# MPPT-v2.net
KiCad netlist of a schematic drawn in Altium Designer
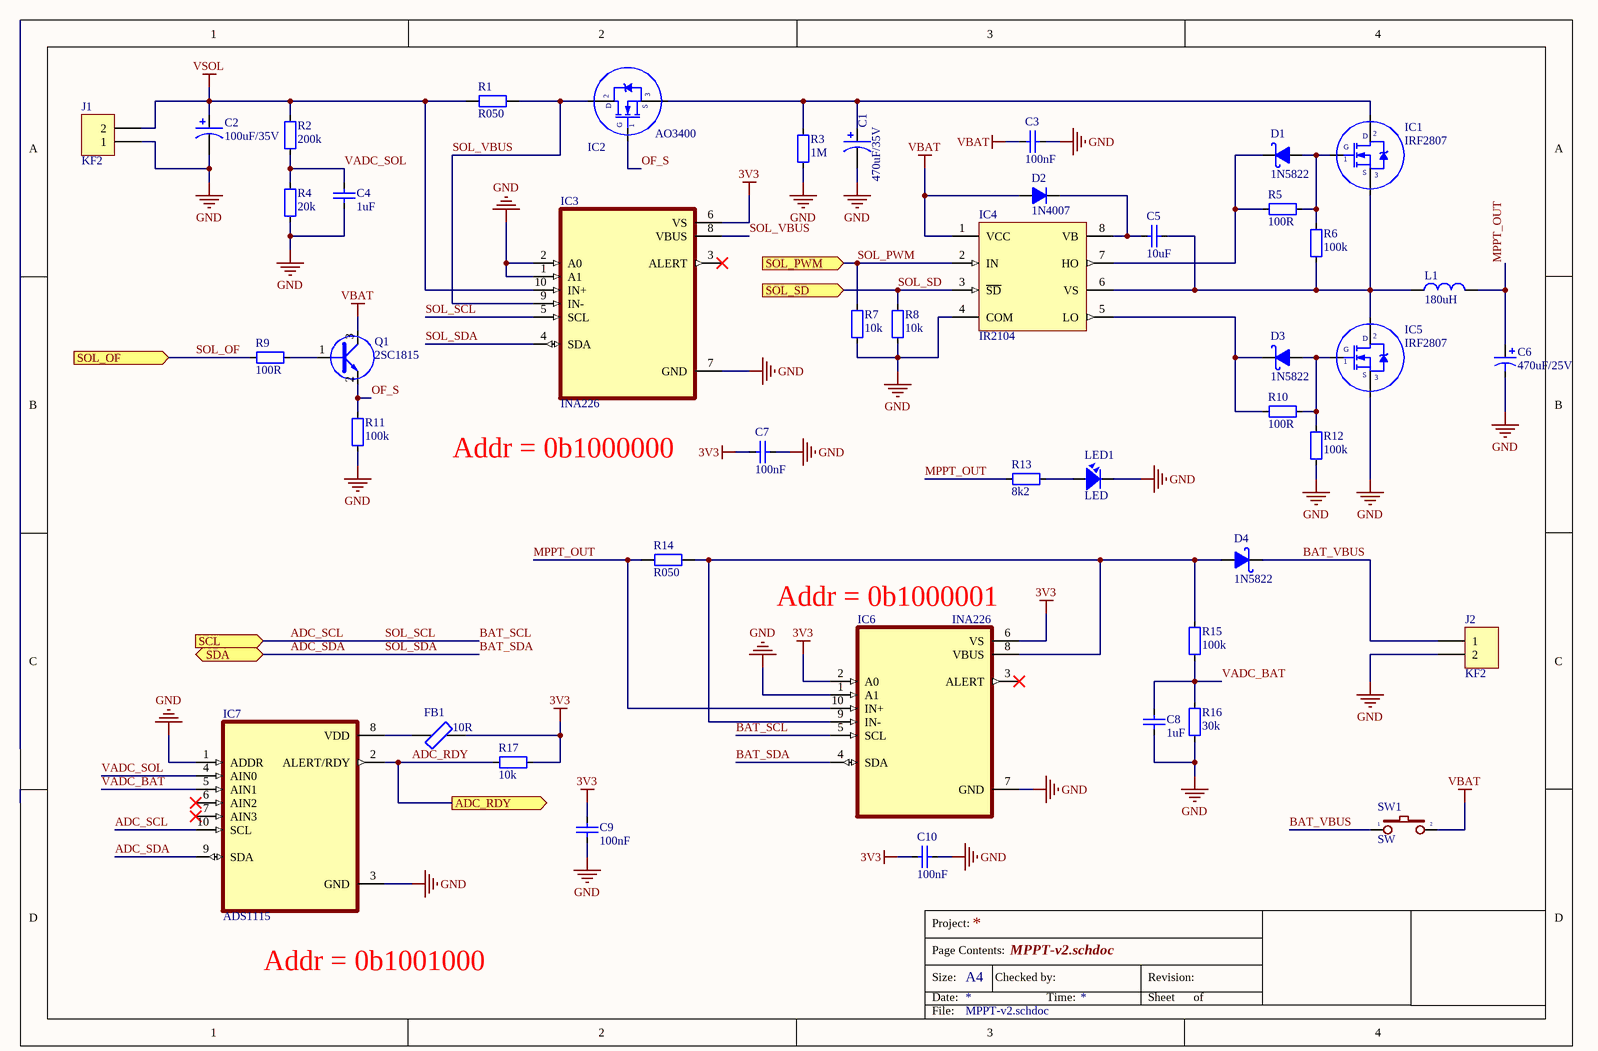
[diagram p0: MPPT-v2.schdoc]

(export (version "E")
  (design (tool "Eeschema 10.0.6"))
  (components
    (comp (ref "C1")
      (value "470uF/35V")
      (footprint "CAP_H17_D10")
      (description "Polarized Capacitor (Axial)")
      (fields (field (name "PUBLISHER") "Altium Limited"))
      (libsource (lib "My Library") (part "Cap Pol"))
    )
    (comp (ref "C2")
      (value "100uF/35V")
      (footprint "CAP_H12_D06")
      (description "Polarized Capacitor (Axial)")
      (fields (field (name "PUBLISHER") "Altium Limited"))
      (libsource (lib "My Library") (part "Cap Pol"))
    )
    (comp (ref "C3")
      (value "100nF")
      (footprint "CAP_0805")
      (description "Capacitor")
      (fields (field (name "PUBLISHER") "Altium Limited"))
      (libsource (lib "My Library") (part "CapSMD"))
    )
    (comp (ref "C4")
      (value "1uF")
      (footprint "CAP_0805")
      (description "Capacitor")
      (fields (field (name "PUBLISHER") "Altium Limited"))
      (libsource (lib "My Library") (part "CapSMD"))
    )
    (comp (ref "C5")
      (value "10uF")
      (footprint "CAP_0805")
      (description "Capacitor")
      (fields (field (name "PUBLISHER") "Altium Limited"))
      (libsource (lib "My Library") (part "CapSMD"))
    )
    (comp (ref "C6")
      (value "470uF/25V")
      (footprint "C8mm")
      (description "Polarized Capacitor (Axial)")
      (fields (field (name "PUBLISHER") "Altium Limited"))
      (libsource (lib "") (part "Cap Pol_1"))
    )
    (comp (ref "C7")
      (value "100nF")
      (footprint "CAP_0805")
      (description "Capacitor")
      (fields (field (name "PUBLISHER") "Altium Limited"))
      (libsource (lib "My Library") (part "CapSMD"))
    )
    (comp (ref "C8")
      (value "1uF")
      (footprint "CAP_0805")
      (description "Capacitor")
      (fields (field (name "PUBLISHER") "Altium Limited"))
      (libsource (lib "My Library") (part "CapSMD"))
    )
    (comp (ref "C9")
      (value "100nF")
      (footprint "CAP_0805")
      (description "Capacitor")
      (fields (field (name "PUBLISHER") "Altium Limited"))
      (libsource (lib "My Library") (part "CapSMD"))
    )
    (comp (ref "C10")
      (value "100nF")
      (footprint "CAP_0805")
      (description "Capacitor")
      (fields (field (name "PUBLISHER") "Altium Limited"))
      (libsource (lib "My Library") (part "CapSMD"))
    )
    (comp (ref "D1")
      (value "1N5822")
      (footprint "DIO-214AC(SMA)")
      (description "Schottky Rectifiers")
      (libsource (lib "My Library") (part "1N5822"))
    )
    (comp (ref "D2")
      (value "1N4007")
      (footprint "DIO-214AC(SMA)")
      (description "Diode 1A")
      (libsource (lib "My Library") (part "D1A"))
    )
    (comp (ref "D3")
      (value "1N5822")
      (footprint "DIO-214AC(SMA)")
      (description "Schottky Rectifiers")
      (libsource (lib "My Library") (part "1N5822"))
    )
    (comp (ref "D4")
      (value "1N5822")
      (footprint "DIO-214AC(SMA)")
      (description "Schottky Rectifiers")
      (libsource (lib "My Library") (part "1N5822"))
    )
    (comp (ref "FB1")
      (value "10R")
      (footprint "RES-SMD-0805")
      (description "Generic Ferrit Bead")
      (libsource (lib "My Library") (part "Ferrit Bead"))
    )
    (comp (ref "IC1")
      (value "IRF2807")
      (footprint "TO-220")
      (description "Generic N Channel MOSFET")
      (libsource (lib "My Library") (part "MOSFET_N"))
    )
    (comp (ref "IC2")
      (value "AO3400")
      (footprint "SOT23A")
      (description "Generic N Channel MOSFET")
      (libsource (lib "My Library") (part "MOSFET_N"))
    )
    (comp (ref "IC3")
      (value "INA226")
      (footprint "VSSOP-10")
      (description "Current Sensing IC")
      (libsource (lib "My Library") (part "INA226"))
    )
    (comp (ref "IC4")
      (value "IR2104")
      (footprint "SOP-8")
      (description "PWM Driver")
      (libsource (lib "My Library") (part "IR2104"))
    )
    (comp (ref "IC5")
      (value "IRF2807")
      (footprint "TO-220")
      (description "Generic N Channel MOSFET")
      (libsource (lib "My Library") (part "MOSFET_N"))
    )
    (comp (ref "IC6")
      (value "INA226")
      (footprint "VSSOP-10")
      (description "Current Sensing IC")
      (libsource (lib "My Library") (part "INA226"))
    )
    (comp (ref "IC7")
      (value "ADS1115")
      (footprint "VSSOP-10")
      (description "16 bits 4 channals ADC IC")
      (libsource (lib "My Library") (part "ADS1115"))
    )
    (comp (ref "J1")
      (value "KF2")
      (footprint "KF2-5.08")
      (fields
        (field (name "MANUFACTURER") "Würth Elektronik eiSos GmbH")
        (field (name "PARTNO") "691103110002")
        (field (name "CREATED BY") "Karrer Zheng")
      )
      (libsource (lib "My Library") (part "KF2"))
    )
    (comp (ref "J2")
      (value "KF2")
      (footprint "KF2-5.08")
      (fields
        (field (name "MANUFACTURER") "Würth Elektronik eiSos GmbH")
        (field (name "PARTNO") "691103110002")
        (field (name "CREATED BY") "Karrer Zheng")
      )
      (libsource (lib "") (part "KF2_1"))
    )
    (comp (ref "L1")
      (value "180uH")
      (footprint "L-DIP-M-13.5x6")
      (description "180uH 4A 13mm")
      (libsource (lib "My Library") (part "Inductor"))
    )
    (comp (ref "LED1")
      (value "LED")
      (footprint "LED-0805-Red")
      (description "LED Single colour Green and Red")
      (libsource (lib "My Library") (part "LED"))
    )
    (comp (ref "Q1")
      (value "2SC1815")
      (footprint "SOT23D")
      (description "NPN 600mW, ECB")
      (libsource (lib "My Library") (part "C1815"))
    )
    (comp (ref "R1")
      (value "R050")
      (footprint "RES-SMD-2512")
      (description "Resistor SMD")
      (fields
        (field (name "MANUFACTURER") "Generic Components")
        (field (name "PUBLISHER") "Altium Hobart Technology Centre")
      )
      (libsource (lib "") (part "Resistor - SMD_1"))
    )
    (comp (ref "R2")
      (value "200k")
      (footprint "RES-SMD-0805")
      (description "Resistor")
      (fields
        (field (name "MANUFACTURER") "Generic Components")
        (field (name "PUBLISHER") "Altium Hobart Technology Centre")
      )
      (libsource (lib "My Library") (part "Resistor - SMD"))
    )
    (comp (ref "R3")
      (value "1M")
      (footprint "RES-SMD-0805")
      (description "Resistor")
      (fields
        (field (name "MANUFACTURER") "Generic Components")
        (field (name "PUBLISHER") "Altium Hobart Technology Centre")
      )
      (libsource (lib "My Library") (part "Resistor - SMD"))
    )
    (comp (ref "R4")
      (value "20k")
      (footprint "RES-SMD-0805")
      (description "Resistor")
      (fields
        (field (name "MANUFACTURER") "Generic Components")
        (field (name "PUBLISHER") "Altium Hobart Technology Centre")
      )
      (libsource (lib "My Library") (part "Resistor - SMD"))
    )
    (comp (ref "R5")
      (value "100R")
      (footprint "RES-SMD-0805")
      (description "Resistor")
      (fields
        (field (name "MANUFACTURER") "Generic Components")
        (field (name "PUBLISHER") "Altium Hobart Technology Centre")
      )
      (libsource (lib "My Library") (part "Resistor - SMD"))
    )
    (comp (ref "R6")
      (value "100k")
      (footprint "RES-SMD-0805")
      (description "Resistor")
      (fields
        (field (name "MANUFACTURER") "Generic Components")
        (field (name "PUBLISHER") "Altium Hobart Technology Centre")
      )
      (libsource (lib "My Library") (part "Resistor - SMD"))
    )
    (comp (ref "R7")
      (value "10k")
      (footprint "RES-SMD-0805")
      (description "Resistor")
      (fields
        (field (name "MANUFACTURER") "Generic Components")
        (field (name "PUBLISHER") "Altium Hobart Technology Centre")
      )
      (libsource (lib "My Library") (part "Resistor - SMD"))
    )
    (comp (ref "R8")
      (value "10k")
      (footprint "RES-SMD-0805")
      (description "Resistor")
      (fields
        (field (name "MANUFACTURER") "Generic Components")
        (field (name "PUBLISHER") "Altium Hobart Technology Centre")
      )
      (libsource (lib "My Library") (part "Resistor - SMD"))
    )
    (comp (ref "R9")
      (value "100R")
      (footprint "RES-SMD-0805")
      (description "Resistor")
      (fields
        (field (name "MANUFACTURER") "Generic Components")
        (field (name "PUBLISHER") "Altium Hobart Technology Centre")
      )
      (libsource (lib "My Library") (part "Resistor - SMD"))
    )
    (comp (ref "R10")
      (value "100R")
      (footprint "RES-SMD-0805")
      (description "Resistor")
      (fields
        (field (name "MANUFACTURER") "Generic Components")
        (field (name "PUBLISHER") "Altium Hobart Technology Centre")
      )
      (libsource (lib "My Library") (part "Resistor - SMD"))
    )
    (comp (ref "R11")
      (value "100k")
      (footprint "RES-SMD-0805")
      (description "Resistor")
      (fields
        (field (name "MANUFACTURER") "Generic Components")
        (field (name "PUBLISHER") "Altium Hobart Technology Centre")
      )
      (libsource (lib "My Library") (part "Resistor - SMD"))
    )
    (comp (ref "R12")
      (value "100k")
      (footprint "RES-SMD-0805")
      (description "Resistor")
      (fields
        (field (name "MANUFACTURER") "Generic Components")
        (field (name "PUBLISHER") "Altium Hobart Technology Centre")
      )
      (libsource (lib "My Library") (part "Resistor - SMD"))
    )
    (comp (ref "R13")
      (value "8k2")
      (footprint "RES-SMD-0805")
      (description "Resistor")
      (fields
        (field (name "MANUFACTURER") "Generic Components")
        (field (name "PUBLISHER") "Altium Hobart Technology Centre")
      )
      (libsource (lib "My Library") (part "Resistor - SMD"))
    )
    (comp (ref "R14")
      (value "R050")
      (footprint "RES-SMD-2512")
      (description "Resistor SMD")
      (fields
        (field (name "MANUFACTURER") "Generic Components")
        (field (name "PUBLISHER") "Altium Hobart Technology Centre")
      )
      (libsource (lib "") (part "Resistor - SMD_1"))
    )
    (comp (ref "R15")
      (value "100k")
      (footprint "RES-SMD-0805")
      (description "Resistor")
      (fields
        (field (name "MANUFACTURER") "Generic Components")
        (field (name "PUBLISHER") "Altium Hobart Technology Centre")
      )
      (libsource (lib "My Library") (part "Resistor - SMD"))
    )
    (comp (ref "R16")
      (value "30k")
      (footprint "RES-SMD-0805")
      (description "Resistor")
      (fields
        (field (name "MANUFACTURER") "Generic Components")
        (field (name "PUBLISHER") "Altium Hobart Technology Centre")
      )
      (libsource (lib "My Library") (part "Resistor - SMD"))
    )
    (comp (ref "R17")
      (value "10k")
      (footprint "RES-SMD-0805")
      (description "Resistor")
      (fields
        (field (name "MANUFACTURER") "Generic Components")
        (field (name "PUBLISHER") "Altium Hobart Technology Centre")
      )
      (libsource (lib "My Library") (part "Resistor - SMD"))
    )
    (comp (ref "SW1")
      (value "SW")
      (footprint "SW2")
      (description "Switch button 2 pin")
      (libsource (lib "My Library") (part "SW2"))
    )
  )
  (nets
    (net (code "1") (name "/ADC_RDY") (class "Default")
      (node (ref "IC7") (pin "2") (pinfunction "ALERT/RDY_2") (pintype "output"))
      (node (ref "R17") (pin "2") (pinfunction "2_2") (pintype "passive"))
    )
    (net (code "2") (name "/ADC_SCL") (class "Default")
      (node (ref "IC3") (pin "5") (pinfunction "SCL_5") (pintype "input"))
      (node (ref "IC6") (pin "5") (pinfunction "SCL_5") (pintype "input"))
      (node (ref "IC7") (pin "10") (pinfunction "SCL_10") (pintype "input"))
    )
    (net (code "3") (name "/ADC_SDA") (class "Default")
      (node (ref "IC3") (pin "4") (pinfunction "SDA_4") (pintype "bidirectional"))
      (node (ref "IC6") (pin "4") (pinfunction "SDA_4") (pintype "bidirectional"))
      (node (ref "IC7") (pin "9") (pinfunction "SDA_9") (pintype "bidirectional"))
    )
    (net (code "4") (name "/BAT_VBUS") (class "Default")
      (node (ref "D4") (pin "2") (pinfunction "K_2") (pintype "passive"))
      (node (ref "J2") (pin "1") (pinfunction "1_1") (pintype "passive"))
      (node (ref "SW1") (pin "1") (pinfunction "1_1") (pintype "passive"))
    )
    (net (code "5") (name "/MPPT_OUT") (class "Default")
      (node (ref "C6") (pin "1") (pinfunction "1_1") (pintype "passive"))
      (node (ref "IC6") (pin "10") (pinfunction "IN+_10") (pintype "input"))
      (node (ref "L1") (pin "2") (pinfunction "2_2") (pintype "passive"))
      (node (ref "R13") (pin "1") (pinfunction "1_1") (pintype "passive"))
      (node (ref "R14") (pin "2") (pinfunction "2_2") (pintype "passive"))
    )
    (net (code "6") (name "/OF_S") (class "Default")
      (node (ref "IC2") (pin "1") (pinfunction "G_1") (pintype "passive"))
      (node (ref "Q1") (pin "2") (pinfunction "E_2") (pintype "passive"))
      (node (ref "R11") (pin "1") (pinfunction "1_1") (pintype "passive"))
    )
    (net (code "7") (name "/SOL_OF") (class "Default")
      (node (ref "R9") (pin "2") (pinfunction "2_2") (pintype "passive"))
    )
    (net (code "8") (name "/SOL_PWM") (class "Default")
      (node (ref "IC4") (pin "2") (pinfunction "IN_2") (pintype "input"))
      (node (ref "R7") (pin "2") (pinfunction "2_2") (pintype "passive"))
    )
    (net (code "9") (name "/SOL_SD") (class "Default")
      (node (ref "IC4") (pin "3") (pinfunction "~{SD}_3") (pintype "input"))
      (node (ref "R8") (pin "2") (pinfunction "2_2") (pintype "passive"))
    )
    (net (code "10") (name "/SOL_VBUS") (class "Default")
      (node (ref "IC2") (pin "2") (pinfunction "D_2") (pintype "passive"))
      (node (ref "IC3") (pin "8") (pinfunction "VBUS_8") (pintype "power_in"))
      (node (ref "IC3") (pin "9") (pinfunction "IN-_9") (pintype "input"))
      (node (ref "R1") (pin "1") (pinfunction "1_1") (pintype "passive"))
    )
    (net (code "11") (name "/VADC_BAT") (class "Default")
      (node (ref "C8") (pin "1") (pinfunction "1_1") (pintype "passive"))
      (node (ref "IC7") (pin "5") (pinfunction "AIN1_5") (pintype "input"))
      (node (ref "R15") (pin "2") (pinfunction "2_2") (pintype "passive"))
      (node (ref "R16") (pin "1") (pinfunction "1_1") (pintype "passive"))
    )
    (net (code "12") (name "/VADC_SOL") (class "Default")
      (node (ref "C4") (pin "1") (pinfunction "1_1") (pintype "passive"))
      (node (ref "IC7") (pin "4") (pinfunction "AIN0_4") (pintype "input"))
      (node (ref "R2") (pin "1") (pinfunction "1_1") (pintype "passive"))
      (node (ref "R4") (pin "1") (pinfunction "1_1") (pintype "passive"))
    )
    (net (code "13") (name "3V3") (class "Default")
      (node (ref "C10") (pin "1") (pinfunction "1_1") (pintype "passive"))
      (node (ref "C7") (pin "1") (pinfunction "1_1") (pintype "passive"))
      (node (ref "C9") (pin "1") (pinfunction "1_1") (pintype "passive"))
      (node (ref "FB1") (pin "2") (pintype "passive"))
      (node (ref "IC3") (pin "6") (pinfunction "VS_6") (pintype "power_in"))
      (node (ref "IC6") (pin "2") (pinfunction "A0_2") (pintype "input"))
      (node (ref "IC6") (pin "6") (pinfunction "VS_6") (pintype "power_in"))
      (node (ref "R17") (pin "1") (pinfunction "1_1") (pintype "passive"))
    )
    (net (code "14") (name "GND") (class "Default")
      (node (ref "C1") (pin "2") (pinfunction "2_2") (pintype "passive"))
      (node (ref "C10") (pin "2") (pinfunction "2_2") (pintype "passive"))
      (node (ref "C2") (pin "2") (pinfunction "2_2") (pintype "passive"))
      (node (ref "C3") (pin "2") (pinfunction "2_2") (pintype "passive"))
      (node (ref "C4") (pin "2") (pinfunction "2_2") (pintype "passive"))
      (node (ref "C6") (pin "2") (pinfunction "2_2") (pintype "passive"))
      (node (ref "C7") (pin "2") (pinfunction "2_2") (pintype "passive"))
      (node (ref "C8") (pin "2") (pinfunction "2_2") (pintype "passive"))
      (node (ref "C9") (pin "2") (pinfunction "2_2") (pintype "passive"))
      (node (ref "IC3") (pin "1") (pinfunction "A1_1") (pintype "input"))
      (node (ref "IC3") (pin "2") (pinfunction "A0_2") (pintype "input"))
      (node (ref "IC3") (pin "7") (pinfunction "GND_7") (pintype "power_in"))
      (node (ref "IC4") (pin "4") (pinfunction "COM_4") (pintype "power_in"))
      (node (ref "IC5") (pin "3") (pinfunction "S_3") (pintype "passive"))
      (node (ref "IC6") (pin "1") (pinfunction "A1_1") (pintype "input"))
      (node (ref "IC6") (pin "7") (pinfunction "GND_7") (pintype "power_in"))
      (node (ref "IC7") (pin "1") (pinfunction "ADDR_1") (pintype "input"))
      (node (ref "IC7") (pin "3") (pinfunction "GND_3") (pintype "power_in"))
      (node (ref "J1") (pin "1") (pinfunction "1_1") (pintype "passive"))
      (node (ref "J2") (pin "2") (pinfunction "2_2") (pintype "passive"))
      (node (ref "LED1") (pin "2") (pinfunction "2_2") (pintype "passive"))
      (node (ref "R11") (pin "2") (pinfunction "2_2") (pintype "passive"))
      (node (ref "R12") (pin "2") (pinfunction "2_2") (pintype "passive"))
      (node (ref "R16") (pin "2") (pinfunction "2_2") (pintype "passive"))
      (node (ref "R3") (pin "1") (pinfunction "1_1") (pintype "passive"))
      (node (ref "R4") (pin "2") (pinfunction "2_2") (pintype "passive"))
      (node (ref "R7") (pin "1") (pinfunction "1_1") (pintype "passive"))
      (node (ref "R8") (pin "1") (pinfunction "1_1") (pintype "passive"))
    )
    (net (code "15") (name "Net-(D1-A)") (class "Default")
      (node (ref "D1") (pin "1") (pinfunction "A_1") (pintype "passive"))
      (node (ref "IC1") (pin "1") (pinfunction "G_1") (pintype "passive"))
      (node (ref "R5") (pin "1") (pinfunction "1_1") (pintype "passive"))
      (node (ref "R6") (pin "1") (pinfunction "1_1") (pintype "passive"))
    )
    (net (code "16") (name "Net-(D1-K)") (class "Default")
      (node (ref "D1") (pin "2") (pinfunction "K_2") (pintype "passive"))
      (node (ref "IC4") (pin "7") (pinfunction "HO_7") (pintype "output"))
      (node (ref "R5") (pin "2") (pinfunction "2_2") (pintype "passive"))
    )
    (net (code "17") (name "Net-(D2-K)") (class "Default")
      (node (ref "C5") (pin "1") (pinfunction "1_1") (pintype "passive"))
      (node (ref "D2") (pin "2") (pinfunction "K_2") (pintype "passive"))
      (node (ref "IC4") (pin "8") (pinfunction "VB_8") (pintype "power_in"))
    )
    (net (code "18") (name "Net-(D3-A)") (class "Default")
      (node (ref "D3") (pin "1") (pinfunction "A_1") (pintype "passive"))
      (node (ref "IC5") (pin "1") (pinfunction "G_1") (pintype "passive"))
      (node (ref "R10") (pin "1") (pinfunction "1_1") (pintype "passive"))
      (node (ref "R12") (pin "1") (pinfunction "1_1") (pintype "passive"))
    )
    (net (code "19") (name "Net-(D3-K)") (class "Default")
      (node (ref "D3") (pin "2") (pinfunction "K_2") (pintype "passive"))
      (node (ref "IC4") (pin "5") (pinfunction "LO_5") (pintype "output"))
      (node (ref "R10") (pin "2") (pinfunction "2_2") (pintype "passive"))
    )
    (net (code "20") (name "Net-(D4-A)") (class "Default")
      (node (ref "D4") (pin "1") (pinfunction "A_1") (pintype "passive"))
      (node (ref "IC6") (pin "8") (pinfunction "VBUS_8") (pintype "power_in"))
      (node (ref "IC6") (pin "9") (pinfunction "IN-_9") (pintype "input"))
      (node (ref "R14") (pin "1") (pinfunction "1_1") (pintype "passive"))
      (node (ref "R15") (pin "1") (pinfunction "1_1") (pintype "passive"))
    )
    (net (code "21") (name "Net-(IC1-D)") (class "Default")
      (node (ref "C1") (pin "1") (pinfunction "1_1") (pintype "passive"))
      (node (ref "IC1") (pin "2") (pinfunction "D_2") (pintype "passive"))
      (node (ref "IC2") (pin "3") (pinfunction "S_3") (pintype "passive"))
      (node (ref "R3") (pin "2") (pinfunction "2_2") (pintype "passive"))
    )
    (net (code "22") (name "Net-(IC1-S)") (class "Default")
      (node (ref "C5") (pin "2") (pinfunction "2_2") (pintype "passive"))
      (node (ref "IC1") (pin "3") (pinfunction "S_3") (pintype "passive"))
      (node (ref "IC4") (pin "6") (pinfunction "VS_6") (pintype "power_in"))
      (node (ref "IC5") (pin "2") (pinfunction "D_2") (pintype "passive"))
      (node (ref "L1") (pin "1") (pinfunction "1_1") (pintype "passive"))
      (node (ref "R6") (pin "2") (pinfunction "2_2") (pintype "passive"))
    )
    (net (code "23") (name "Net-(IC7-VDD)") (class "Default")
      (node (ref "FB1") (pin "1") (pintype "passive"))
      (node (ref "IC7") (pin "8") (pinfunction "VDD_8") (pintype "power_in"))
    )
    (net (code "24") (name "Net-(LED1-Pad1)") (class "Default")
      (node (ref "LED1") (pin "1") (pinfunction "1_1") (pintype "passive"))
      (node (ref "R13") (pin "2") (pinfunction "2_2") (pintype "passive"))
    )
    (net (code "25") (name "Net-(Q1-B)") (class "Default")
      (node (ref "Q1") (pin "1") (pinfunction "B_1") (pintype "passive"))
      (node (ref "R9") (pin "1") (pinfunction "1_1") (pintype "passive"))
    )
    (net (code "26") (name "VBAT") (class "Default")
      (node (ref "C3") (pin "1") (pinfunction "1_1") (pintype "passive"))
      (node (ref "D2") (pin "1") (pinfunction "A_1") (pintype "passive"))
      (node (ref "IC4") (pin "1") (pinfunction "VCC_1") (pintype "power_in"))
      (node (ref "Q1") (pin "3") (pinfunction "C_3") (pintype "passive"))
      (node (ref "SW1") (pin "2") (pinfunction "2_2") (pintype "passive"))
    )
    (net (code "27") (name "VSOL") (class "Default")
      (node (ref "C2") (pin "1") (pinfunction "1_1") (pintype "passive"))
      (node (ref "IC3") (pin "10") (pinfunction "IN+_10") (pintype "input"))
      (node (ref "J1") (pin "2") (pinfunction "2_2") (pintype "passive"))
      (node (ref "R1") (pin "2") (pinfunction "2_2") (pintype "passive"))
      (node (ref "R2") (pin "2") (pinfunction "2_2") (pintype "passive"))
    )
    (net (code "28") (name "unconnected-(IC3-ALERT-Pad3)") (class "Default")
      (node (ref "IC3") (pin "3") (pinfunction "ALERT_3") (pintype "output+no_connect"))
    )
    (net (code "29") (name "unconnected-(IC6-ALERT-Pad3)") (class "Default")
      (node (ref "IC6") (pin "3") (pinfunction "ALERT_3") (pintype "output+no_connect"))
    )
    (net (code "30") (name "unconnected-(IC7-AIN2-Pad6)") (class "Default")
      (node (ref "IC7") (pin "6") (pinfunction "AIN2_6") (pintype "input+no_connect"))
    )
    (net (code "31") (name "unconnected-(IC7-AIN3-Pad7)") (class "Default")
      (node (ref "IC7") (pin "7") (pinfunction "AIN3_7") (pintype "input+no_connect"))
    )
  )
)
